# x9c.net
KiCad netlist of a schematic drawn in EAGLE
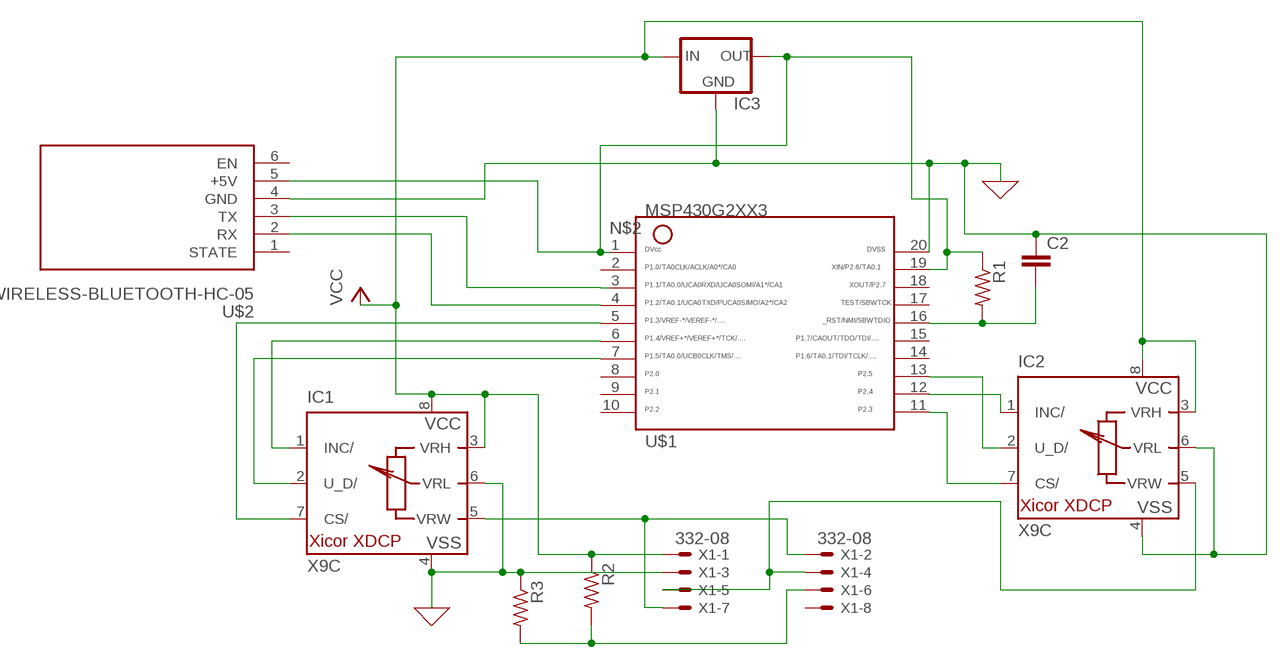
[diagram p0: schematic, sheet 1]

(export (version "E")
  (design (tool "Eeschema 10.0.6"))
  (components
    (comp (ref "C2")
      (value "C2,5-3")
      (footprint "eagle-import:C2.5-3")
      (libsource (lib "eagle-import") (part "C2,5-3"))
    )
    (comp (ref "IC1")
      (value "X9C")
      (footprint "eagle-import:DIL08")
      (libsource (lib "eagle-import") (part "X9C"))
    )
    (comp (ref "IC2")
      (value "X9C")
      (footprint "eagle-import:DIL08")
      (libsource (lib "eagle-import") (part "X9C"))
    )
    (comp (ref "IC3")
      (value "78MXXL")
      (footprint "eagle-import:78MXXL")
      (libsource (lib "eagle-import") (part "78MXXL"))
    )
    (comp (ref "R1")
      (value "R-US_0204/5")
      (footprint "eagle-import:0204_5")
      (libsource (lib "eagle-import") (part "R-US_0204/5"))
    )
    (comp (ref "R2")
      (value "R-US_0204/5")
      (footprint "eagle-import:0204_5")
      (libsource (lib "eagle-import") (part "R-US_0204/5"))
    )
    (comp (ref "R3")
      (value "R-US_0204/5")
      (footprint "eagle-import:0204_5")
      (libsource (lib "eagle-import") (part "R-US_0204/5"))
    )
    (comp (ref "U$1")
      (value "G2XX3---N20")
      (footprint "eagle-import:N20")
      (libsource (lib "eagle-import") (part "G2XX3---N20"))
    )
    (comp (ref "U$2")
      (value "WIRELESS-BLUETOOTH-HC-05")
      (footprint "eagle-import:WIRELESS-BLUETOOTH-HC-05")
      (libsource (lib "eagle-import") (part "WIRELESS-BLUETOOTH-HC-05"))
    )
    (comp (ref "X1")
      (value "332-08")
      (footprint "eagle-import:332-08")
      (libsource (lib "eagle-import") (part "332-08"))
    )
  )
  (nets
    (net (code "1") (name "/N$2") (class "Default")
      (node (ref "IC3") (pin "OUT") (pinfunction "OUT_OUT") (pintype "passive"))
      (node (ref "R1") (pin "1") (pinfunction "1_1") (pintype "passive"))
      (node (ref "U$1") (pin "1") (pinfunction "1_1") (pintype "bidirectional"))
      (node (ref "U$1") (pin "19") (pinfunction "19_19") (pintype "bidirectional"))
      (node (ref "U$2") (pin "5") (pinfunction "+5V_5") (pintype "power_in"))
    )
    (net (code "2") (name "GND") (class "Default")
      (node (ref "C2") (pin "1") (pinfunction "1_1") (pintype "passive"))
      (node (ref "IC1") (pin "4") (pinfunction "VSS_4") (pintype "power_in"))
      (node (ref "IC1") (pin "6") (pinfunction "VRL_6") (pintype "passive"))
      (node (ref "IC2") (pin "4") (pinfunction "VSS_4") (pintype "power_in"))
      (node (ref "IC2") (pin "6") (pinfunction "VRL_6") (pintype "passive"))
      (node (ref "IC3") (pin "GND") (pinfunction "GND_GND") (pintype "input"))
      (node (ref "R3") (pin "1") (pinfunction "1_1") (pintype "passive"))
      (node (ref "U$1") (pin "20") (pinfunction "20_20") (pintype "bidirectional"))
      (node (ref "U$2") (pin "4") (pinfunction "GND_4") (pintype "power_in"))
      (node (ref "X1") (pin "3") (pinfunction "S_3") (pintype "passive"))
    )
    (net (code "3") (name "Net-(C2-Pad2)") (class "Default")
      (node (ref "C2") (pin "2") (pinfunction "2_2") (pintype "passive"))
      (node (ref "R1") (pin "2") (pinfunction "2_2") (pintype "passive"))
      (node (ref "U$1") (pin "16") (pinfunction "16_16") (pintype "bidirectional"))
    )
    (net (code "4") (name "Net-(IC1-CS{slash})") (class "Default")
      (node (ref "IC1") (pin "7") (pinfunction "CS/_7") (pintype "input"))
      (node (ref "U$1") (pin "5") (pinfunction "5_5") (pintype "bidirectional"))
    )
    (net (code "5") (name "Net-(IC1-INC{slash})") (class "Default")
      (node (ref "IC1") (pin "1") (pinfunction "INC/_1") (pintype "input"))
      (node (ref "U$1") (pin "6") (pinfunction "6_6") (pintype "bidirectional"))
    )
    (net (code "6") (name "Net-(IC1-U_D{slash})") (class "Default")
      (node (ref "IC1") (pin "2") (pinfunction "U_D/_2") (pintype "input"))
      (node (ref "U$1") (pin "7") (pinfunction "7_7") (pintype "bidirectional"))
    )
    (net (code "7") (name "Net-(IC1-VRW)") (class "Default")
      (node (ref "IC1") (pin "5") (pinfunction "VRW_5") (pintype "passive"))
      (node (ref "X1") (pin "2") (pinfunction "S_2") (pintype "passive"))
      (node (ref "X1") (pin "7") (pinfunction "S_7") (pintype "passive"))
    )
    (net (code "8") (name "Net-(IC2-CS{slash})") (class "Default")
      (node (ref "IC2") (pin "7") (pinfunction "CS/_7") (pintype "input"))
      (node (ref "U$1") (pin "11") (pinfunction "11_11") (pintype "bidirectional"))
    )
    (net (code "9") (name "Net-(IC2-INC{slash})") (class "Default")
      (node (ref "IC2") (pin "1") (pinfunction "INC/_1") (pintype "input"))
      (node (ref "U$1") (pin "12") (pinfunction "12_12") (pintype "bidirectional"))
    )
    (net (code "10") (name "Net-(IC2-U_D{slash})") (class "Default")
      (node (ref "IC2") (pin "2") (pinfunction "U_D/_2") (pintype "input"))
      (node (ref "U$1") (pin "13") (pinfunction "13_13") (pintype "bidirectional"))
    )
    (net (code "11") (name "Net-(IC2-VRW)") (class "Default")
      (node (ref "IC2") (pin "5") (pinfunction "VRW_5") (pintype "passive"))
      (node (ref "X1") (pin "4") (pinfunction "S_4") (pintype "passive"))
      (node (ref "X1") (pin "5") (pinfunction "S_5") (pintype "passive"))
    )
    (net (code "12") (name "Net-(U$2-RX)") (class "Default")
      (node (ref "U$1") (pin "4") (pinfunction "4_4") (pintype "bidirectional"))
      (node (ref "U$2") (pin "2") (pinfunction "RX_2") (pintype "bidirectional"))
    )
    (net (code "13") (name "Net-(U$2-TX)") (class "Default")
      (node (ref "U$1") (pin "3") (pinfunction "3_3") (pintype "bidirectional"))
      (node (ref "U$2") (pin "3") (pinfunction "TX_3") (pintype "bidirectional"))
    )
    (net (code "14") (name "Net-(X1F-S)") (class "Default")
      (node (ref "R2") (pin "2") (pinfunction "2_2") (pintype "passive"))
      (node (ref "R3") (pin "2") (pinfunction "2_2") (pintype "passive"))
      (node (ref "X1") (pin "6") (pinfunction "S_6") (pintype "passive"))
    )
    (net (code "15") (name "VCC") (class "Default")
      (node (ref "IC1") (pin "3") (pinfunction "VRH_3") (pintype "passive"))
      (node (ref "IC1") (pin "8") (pinfunction "VCC_8") (pintype "power_in"))
      (node (ref "IC2") (pin "3") (pinfunction "VRH_3") (pintype "passive"))
      (node (ref "IC2") (pin "8") (pinfunction "VCC_8") (pintype "power_in"))
      (node (ref "IC3") (pin "IN") (pinfunction "IN_IN") (pintype "input"))
      (node (ref "R2") (pin "1") (pinfunction "1_1") (pintype "passive"))
      (node (ref "X1") (pin "1") (pinfunction "S_1") (pintype "passive"))
    )
    (net (code "16") (name "unconnected-(U$1-Pad2)") (class "Default")
      (node (ref "U$1") (pin "2") (pinfunction "2_2") (pintype "bidirectional"))
    )
    (net (code "17") (name "unconnected-(U$1-Pad8)") (class "Default")
      (node (ref "U$1") (pin "8") (pinfunction "8_8") (pintype "bidirectional"))
    )
    (net (code "18") (name "unconnected-(U$1-Pad9)") (class "Default")
      (node (ref "U$1") (pin "9") (pinfunction "9_9") (pintype "bidirectional"))
    )
    (net (code "19") (name "unconnected-(U$1-Pad10)") (class "Default")
      (node (ref "U$1") (pin "10") (pinfunction "10_10") (pintype "bidirectional"))
    )
    (net (code "20") (name "unconnected-(U$1-Pad14)") (class "Default")
      (node (ref "U$1") (pin "14") (pinfunction "14_14") (pintype "bidirectional"))
    )
    (net (code "21") (name "unconnected-(U$1-Pad15)") (class "Default")
      (node (ref "U$1") (pin "15") (pinfunction "15_15") (pintype "bidirectional"))
    )
    (net (code "22") (name "unconnected-(U$1-Pad17)") (class "Default")
      (node (ref "U$1") (pin "17") (pinfunction "17_17") (pintype "bidirectional"))
    )
    (net (code "23") (name "unconnected-(U$1-Pad18)") (class "Default")
      (node (ref "U$1") (pin "18") (pinfunction "18_18") (pintype "bidirectional"))
    )
    (net (code "24") (name "unconnected-(U$2-EN-Pad6)") (class "Default")
      (node (ref "U$2") (pin "6") (pinfunction "EN_6") (pintype "bidirectional"))
    )
    (net (code "25") (name "unconnected-(U$2-STATE-Pad1)") (class "Default")
      (node (ref "U$2") (pin "1") (pinfunction "STATE_1") (pintype "bidirectional"))
    )
    (net (code "26") (name "unconnected-(X1H-S-Pad8)") (class "Default")
      (node (ref "X1") (pin "8") (pinfunction "S_8") (pintype "passive"))
    )
  )
)
